# Athena-r1p0.net
KiCad netlist of a schematic drawn in EAGLE
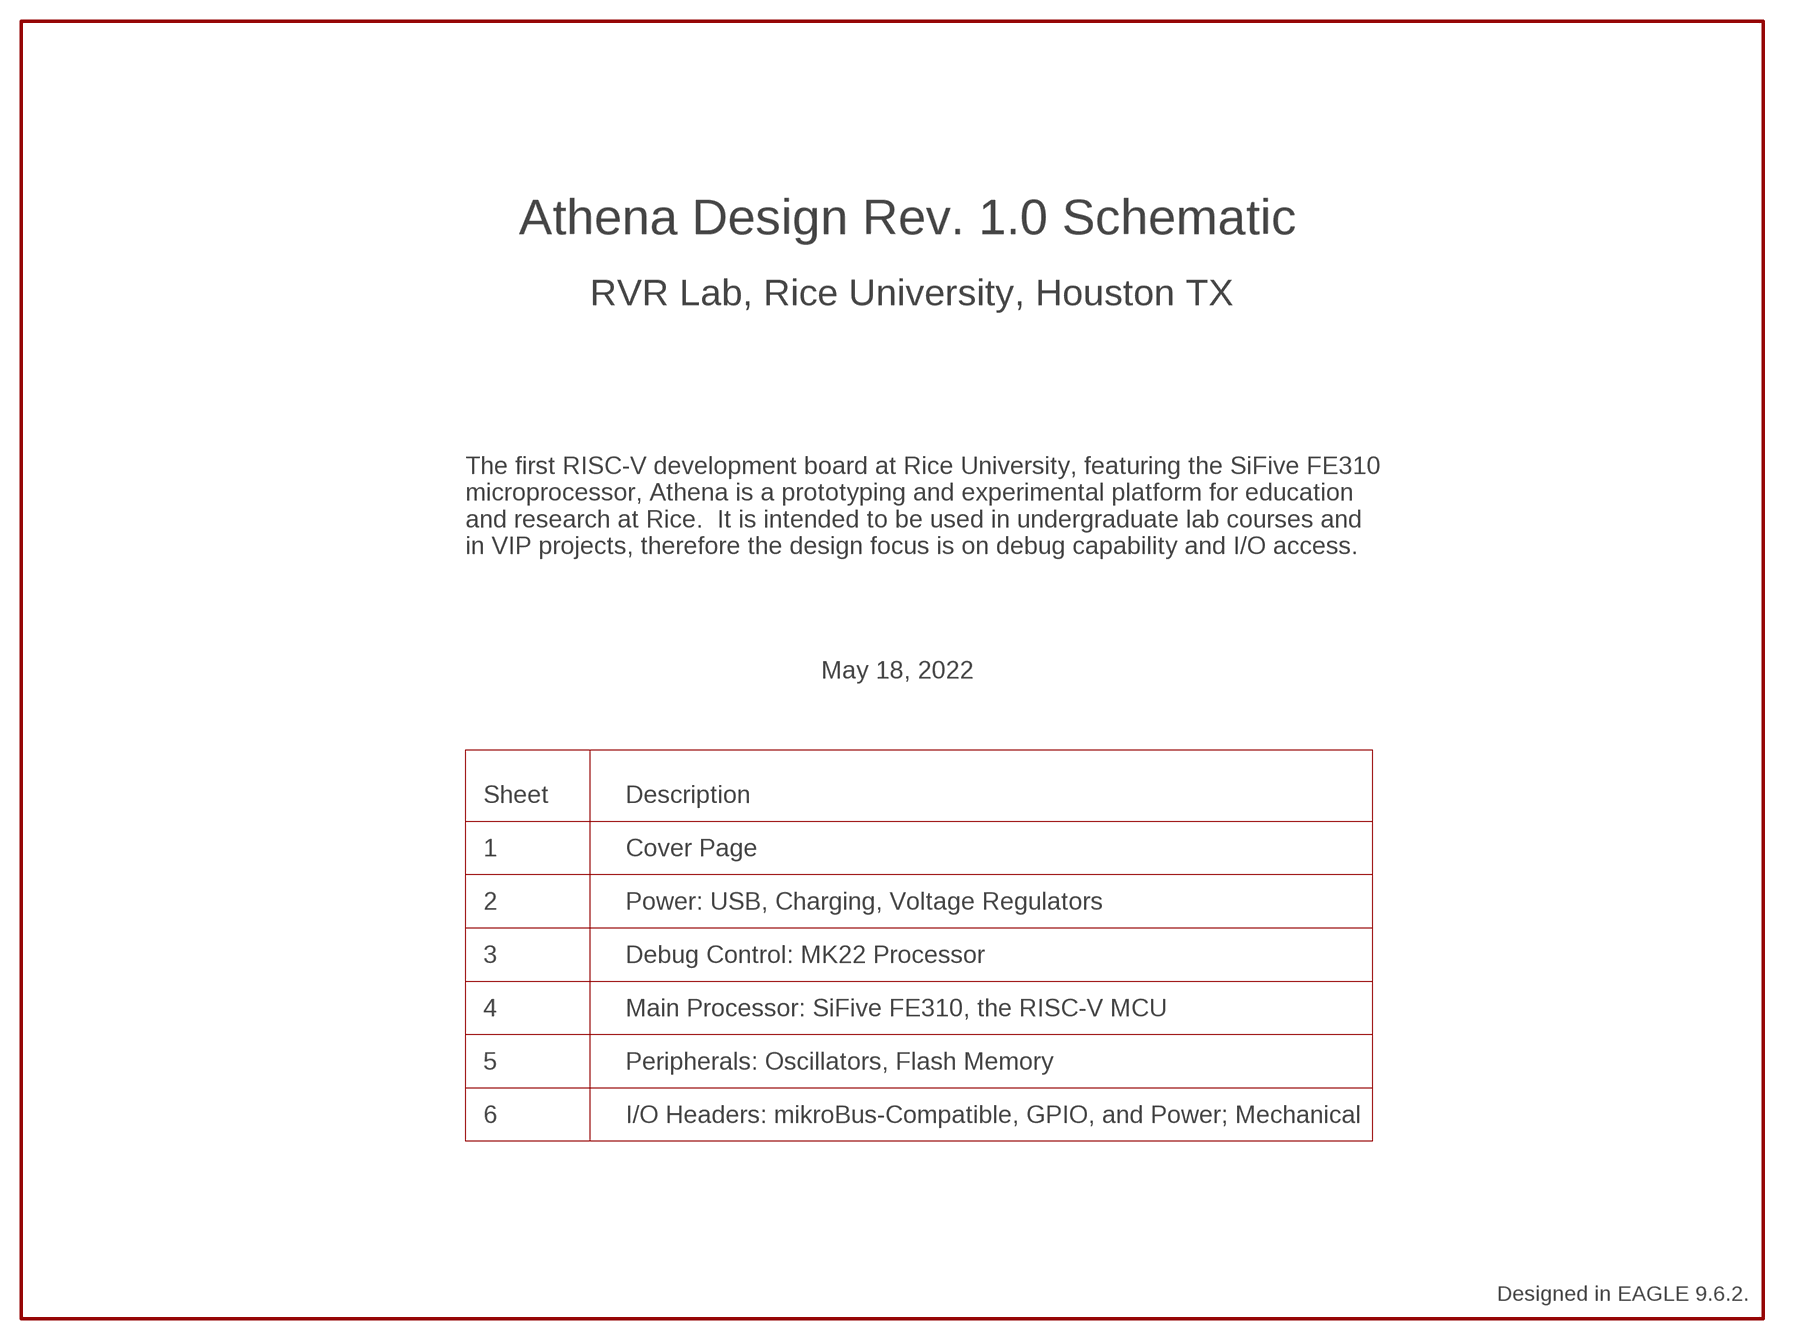
[diagram p0: schematic, sheet 1]
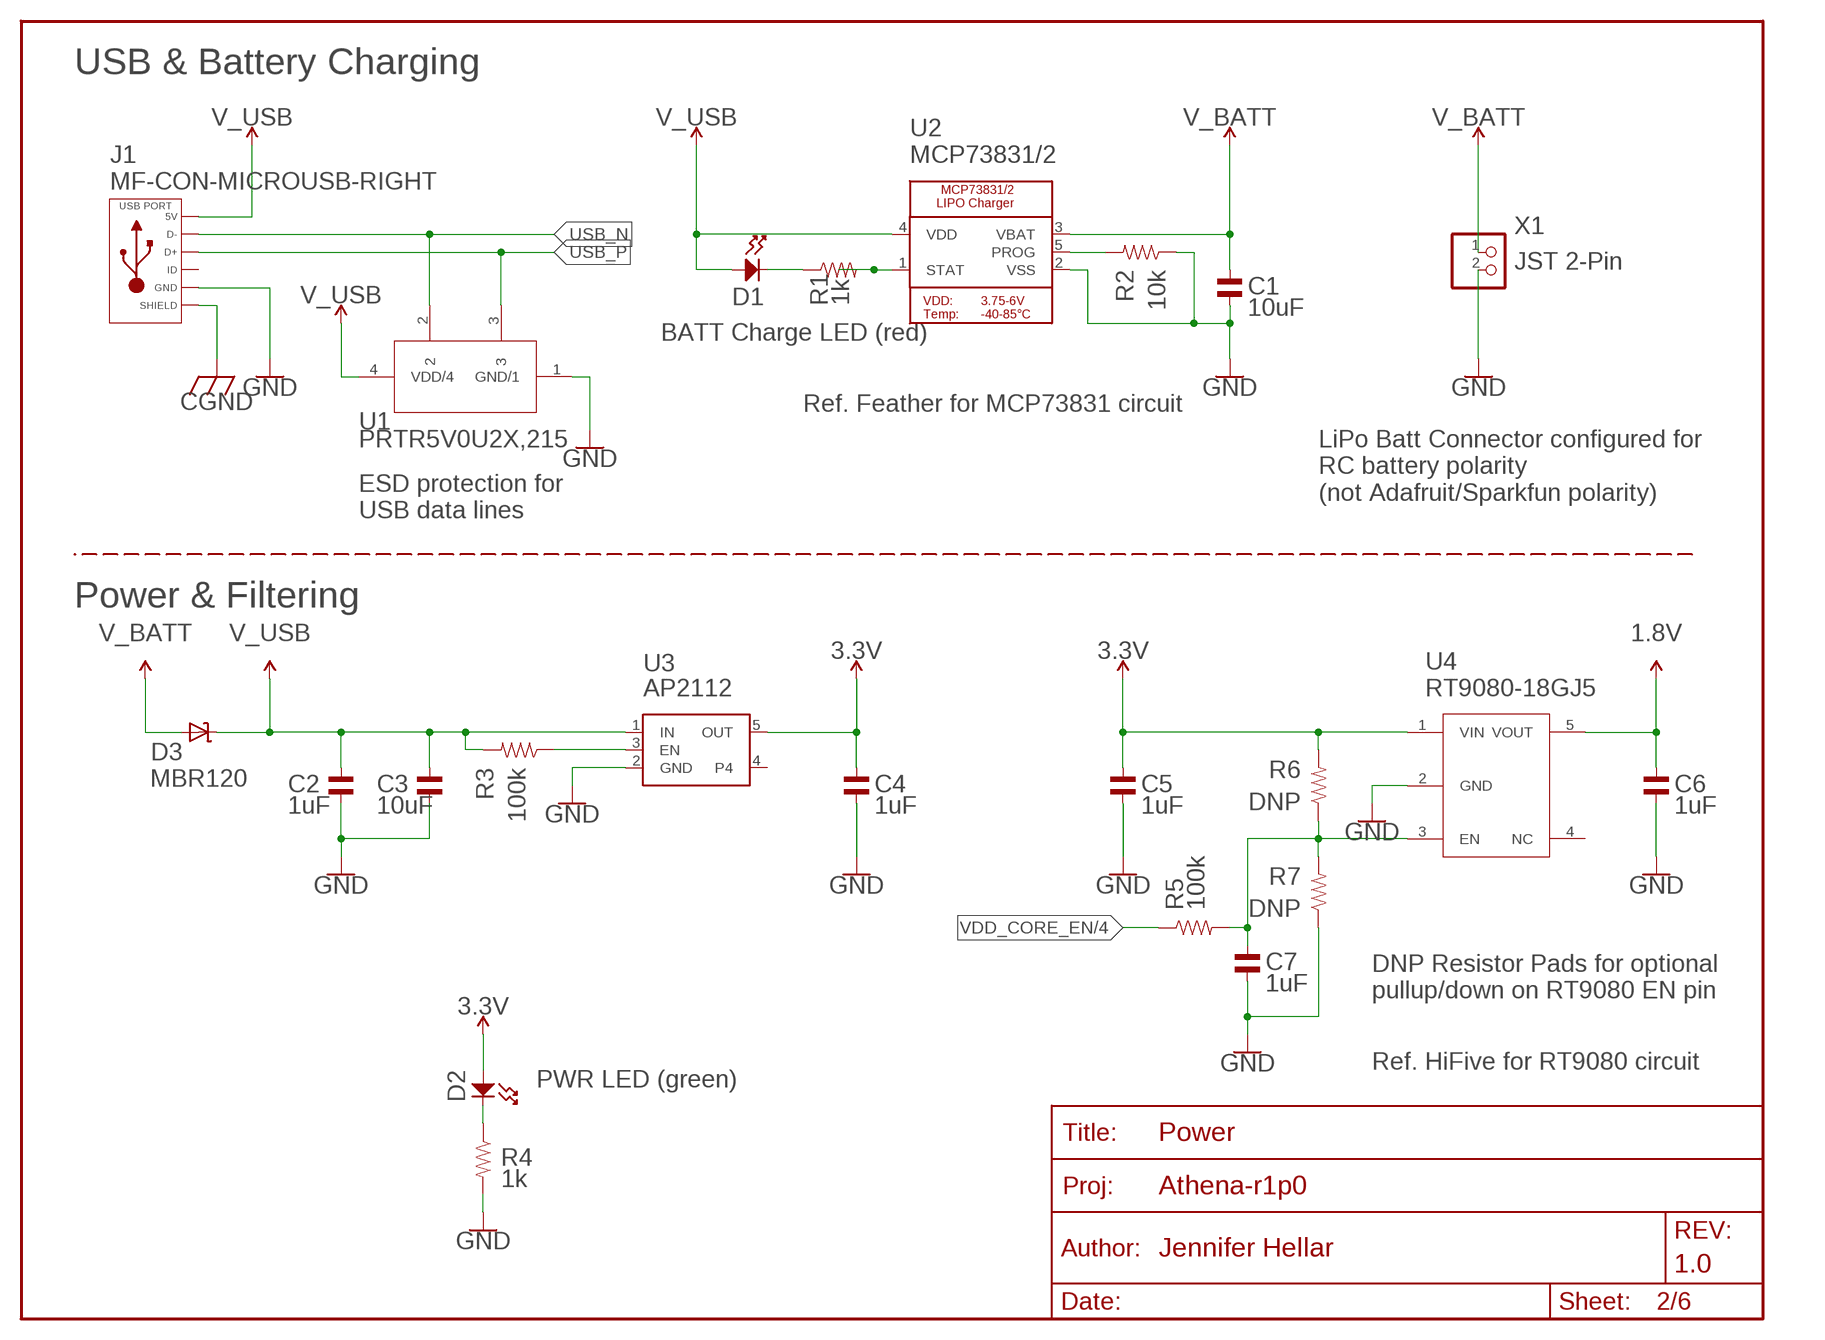
[diagram p1: schematic, sheet 2]
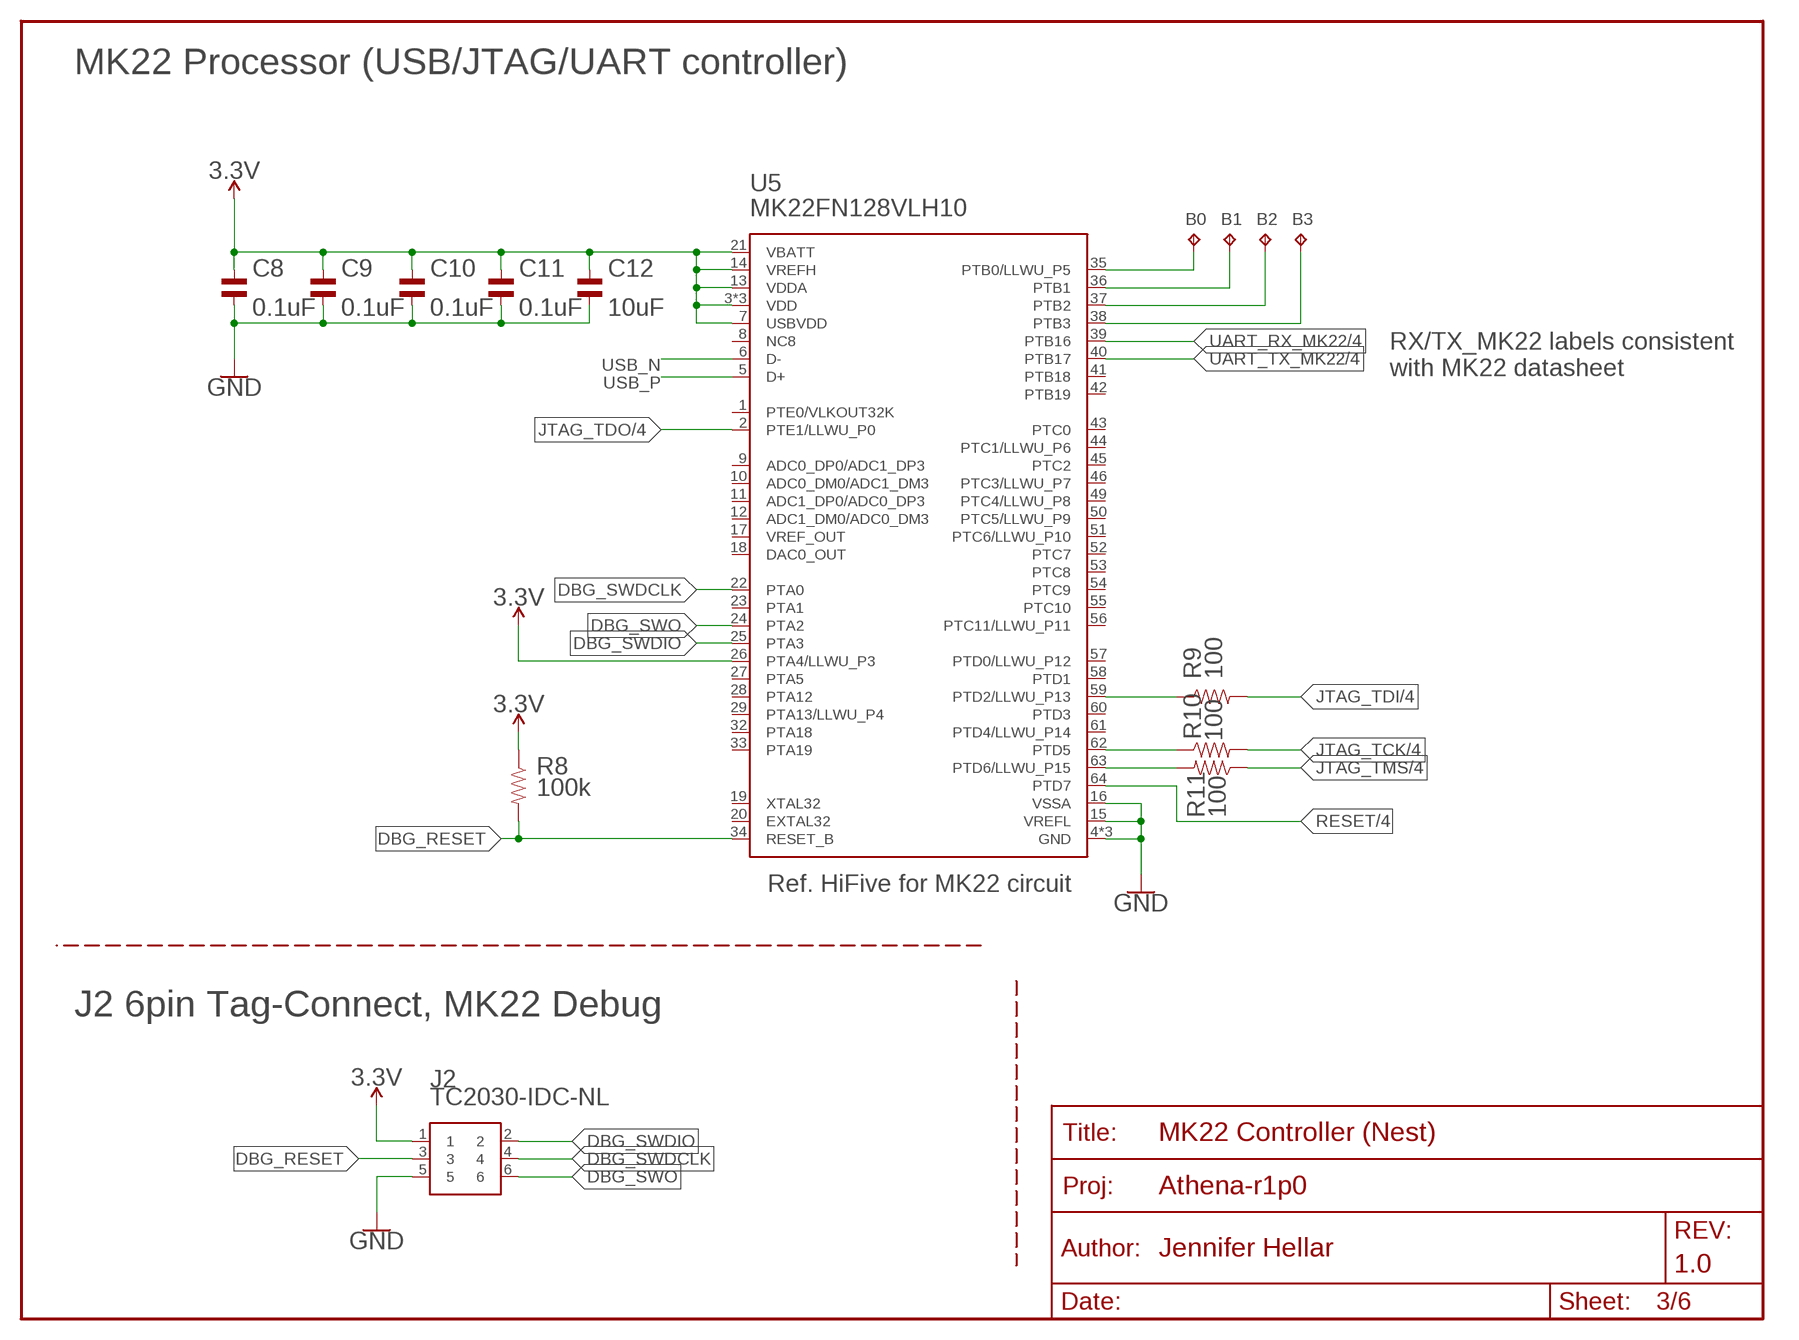
[diagram p2: schematic, sheet 3]
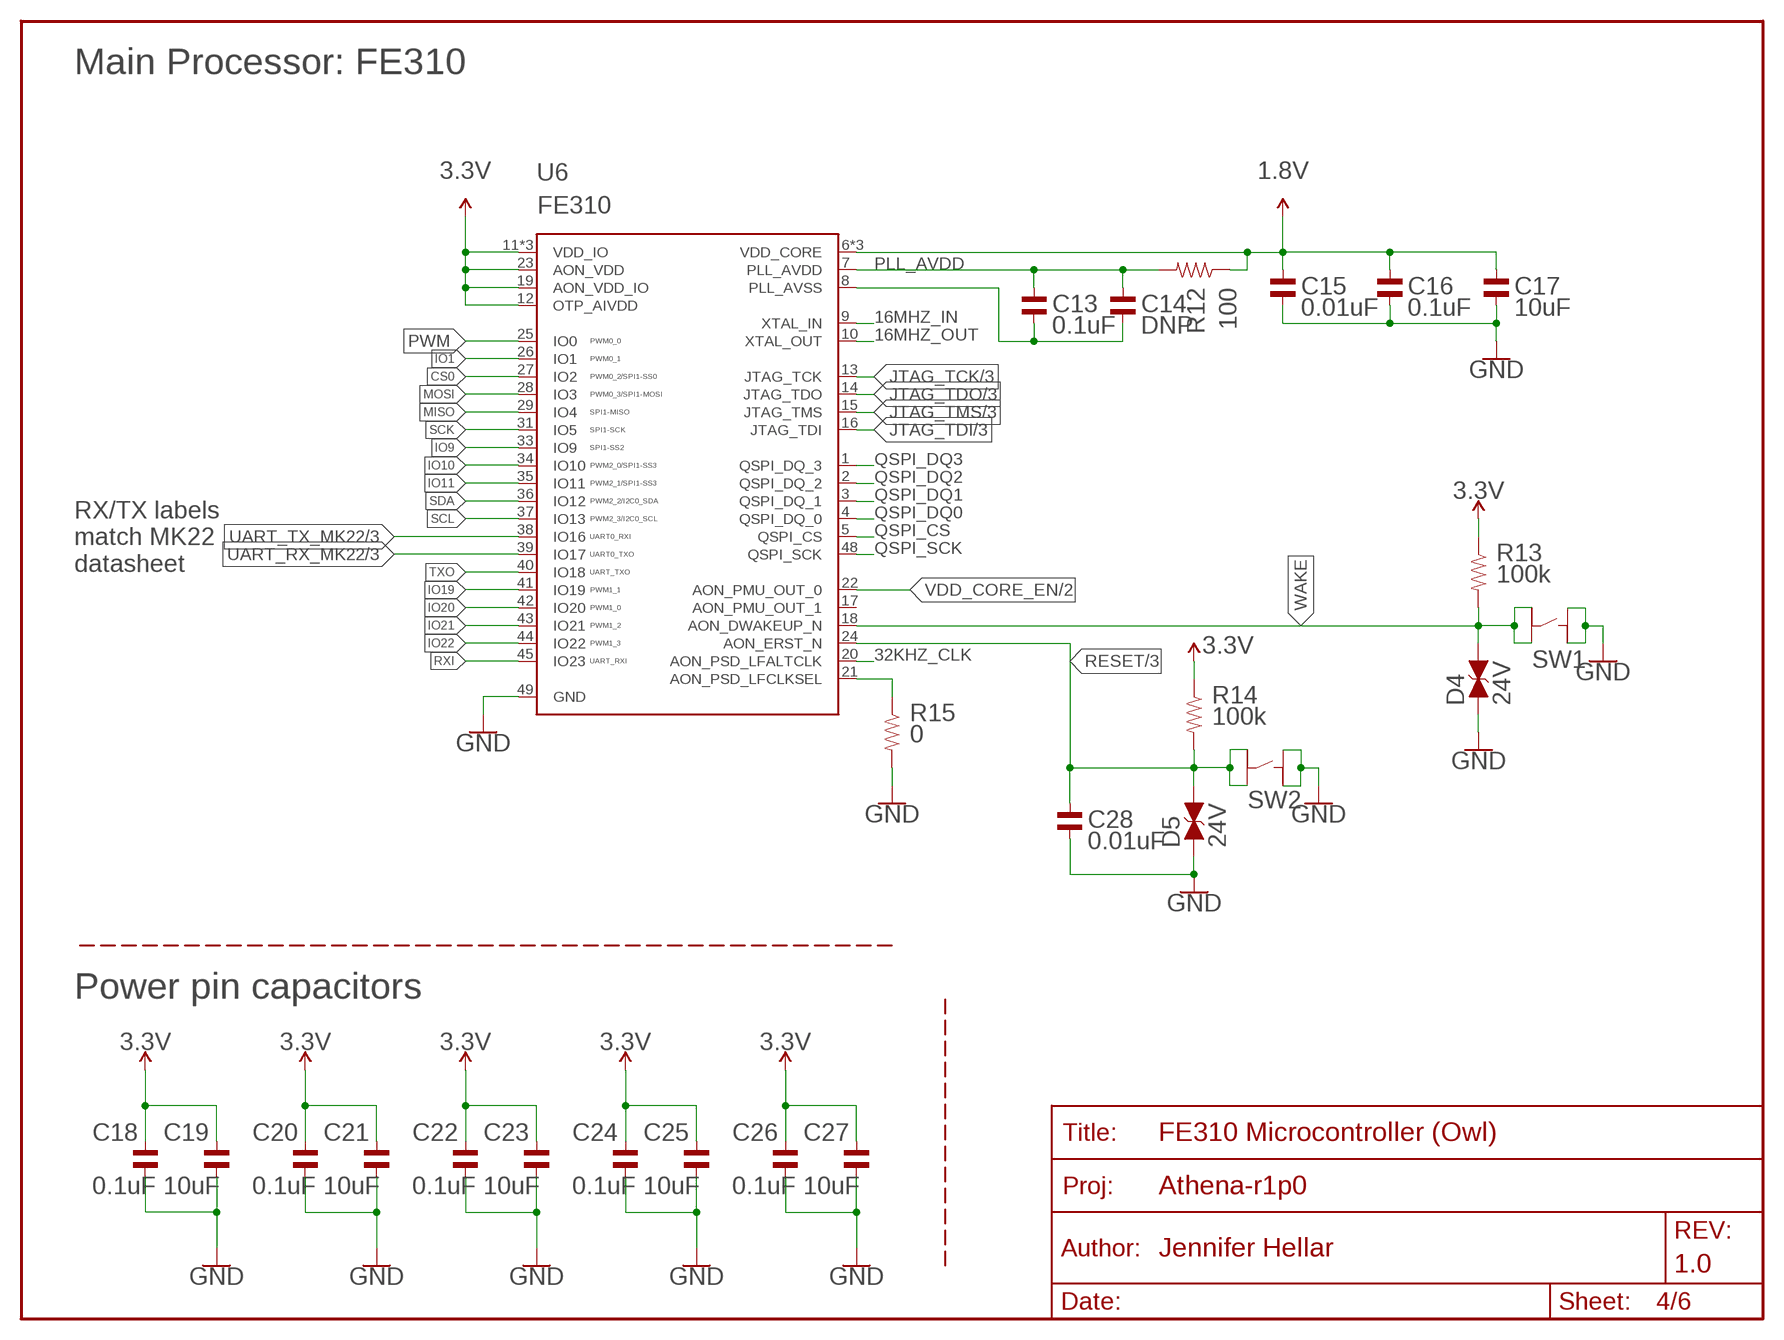
[diagram p3: schematic, sheet 4]
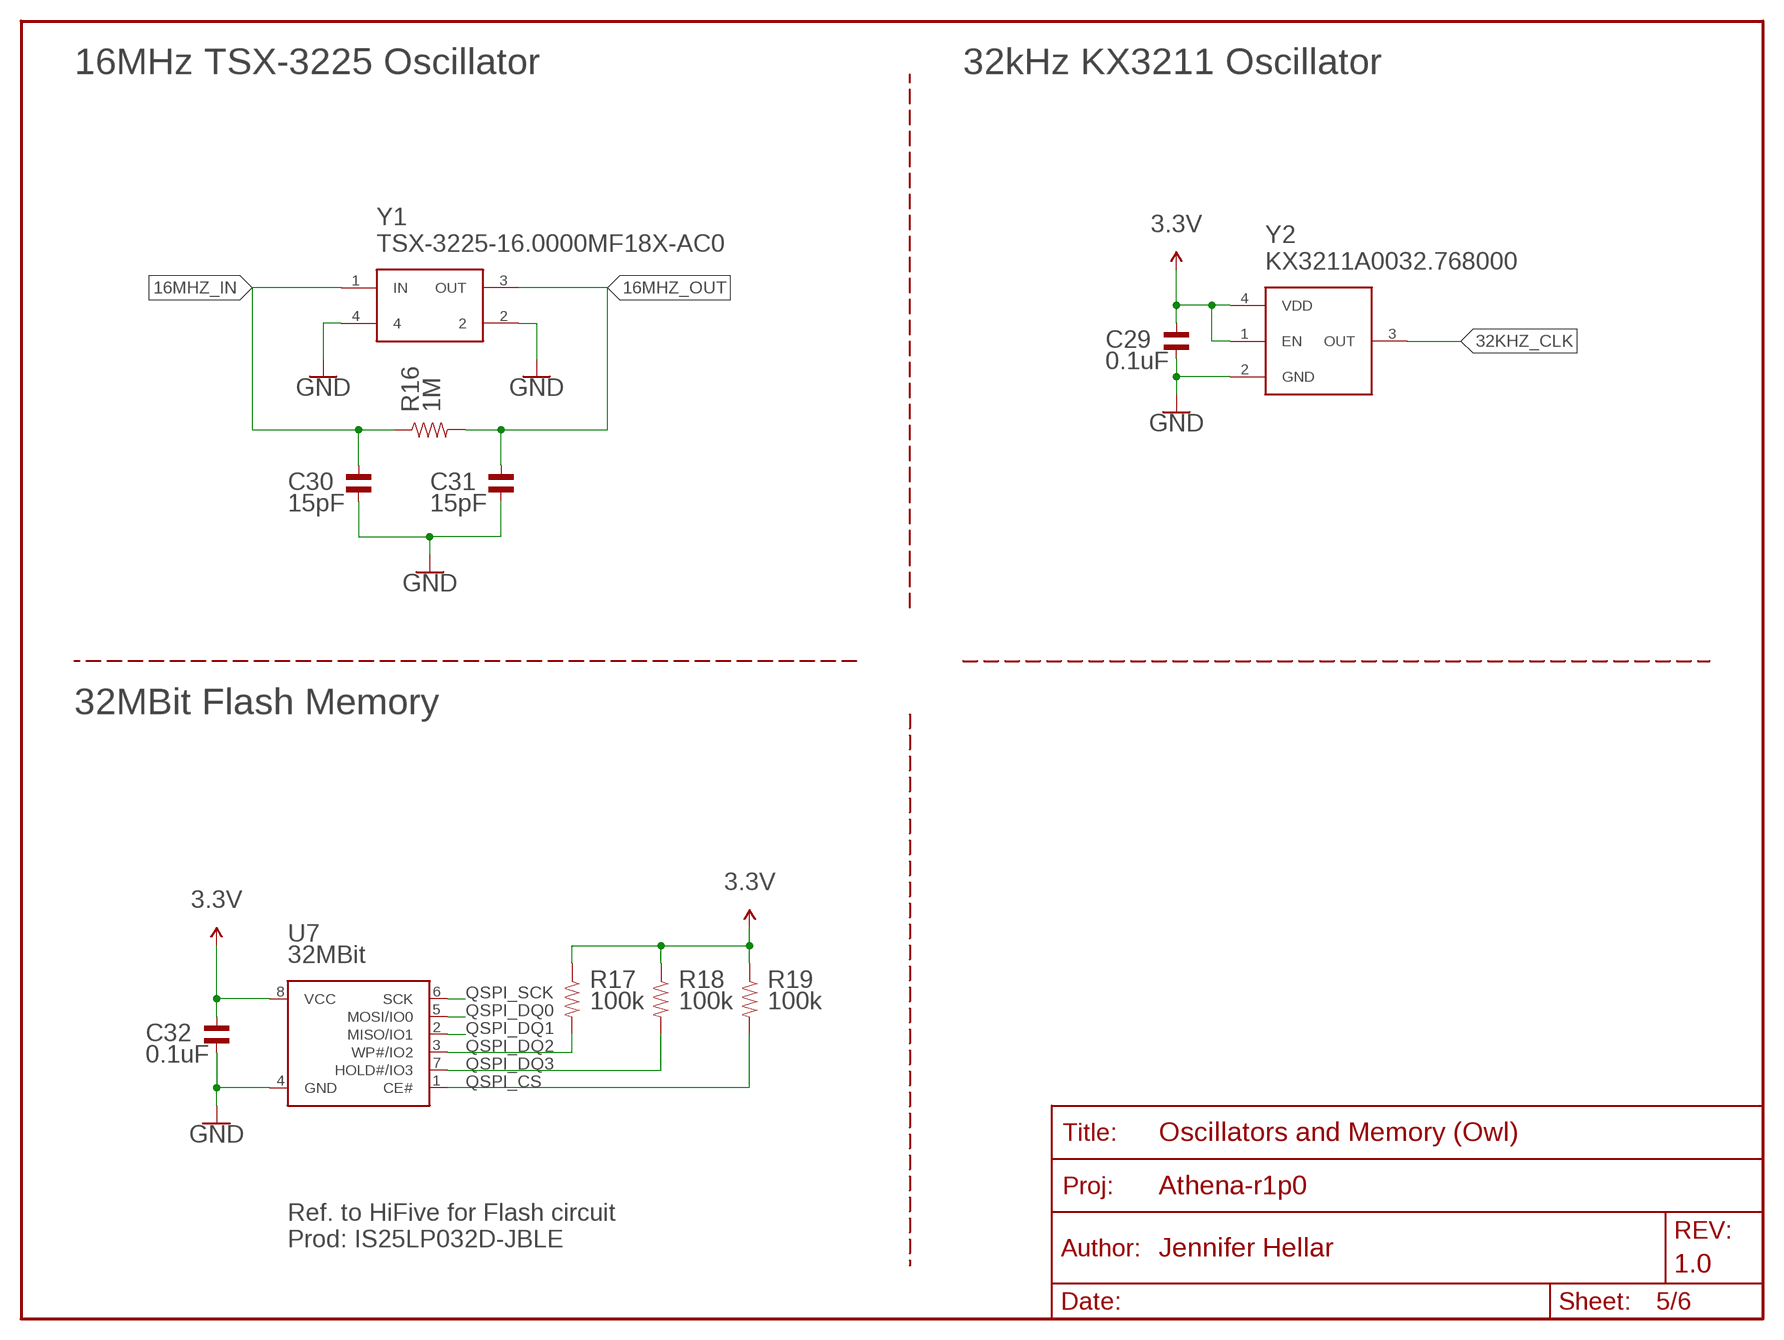
[diagram p4: schematic, sheet 5]
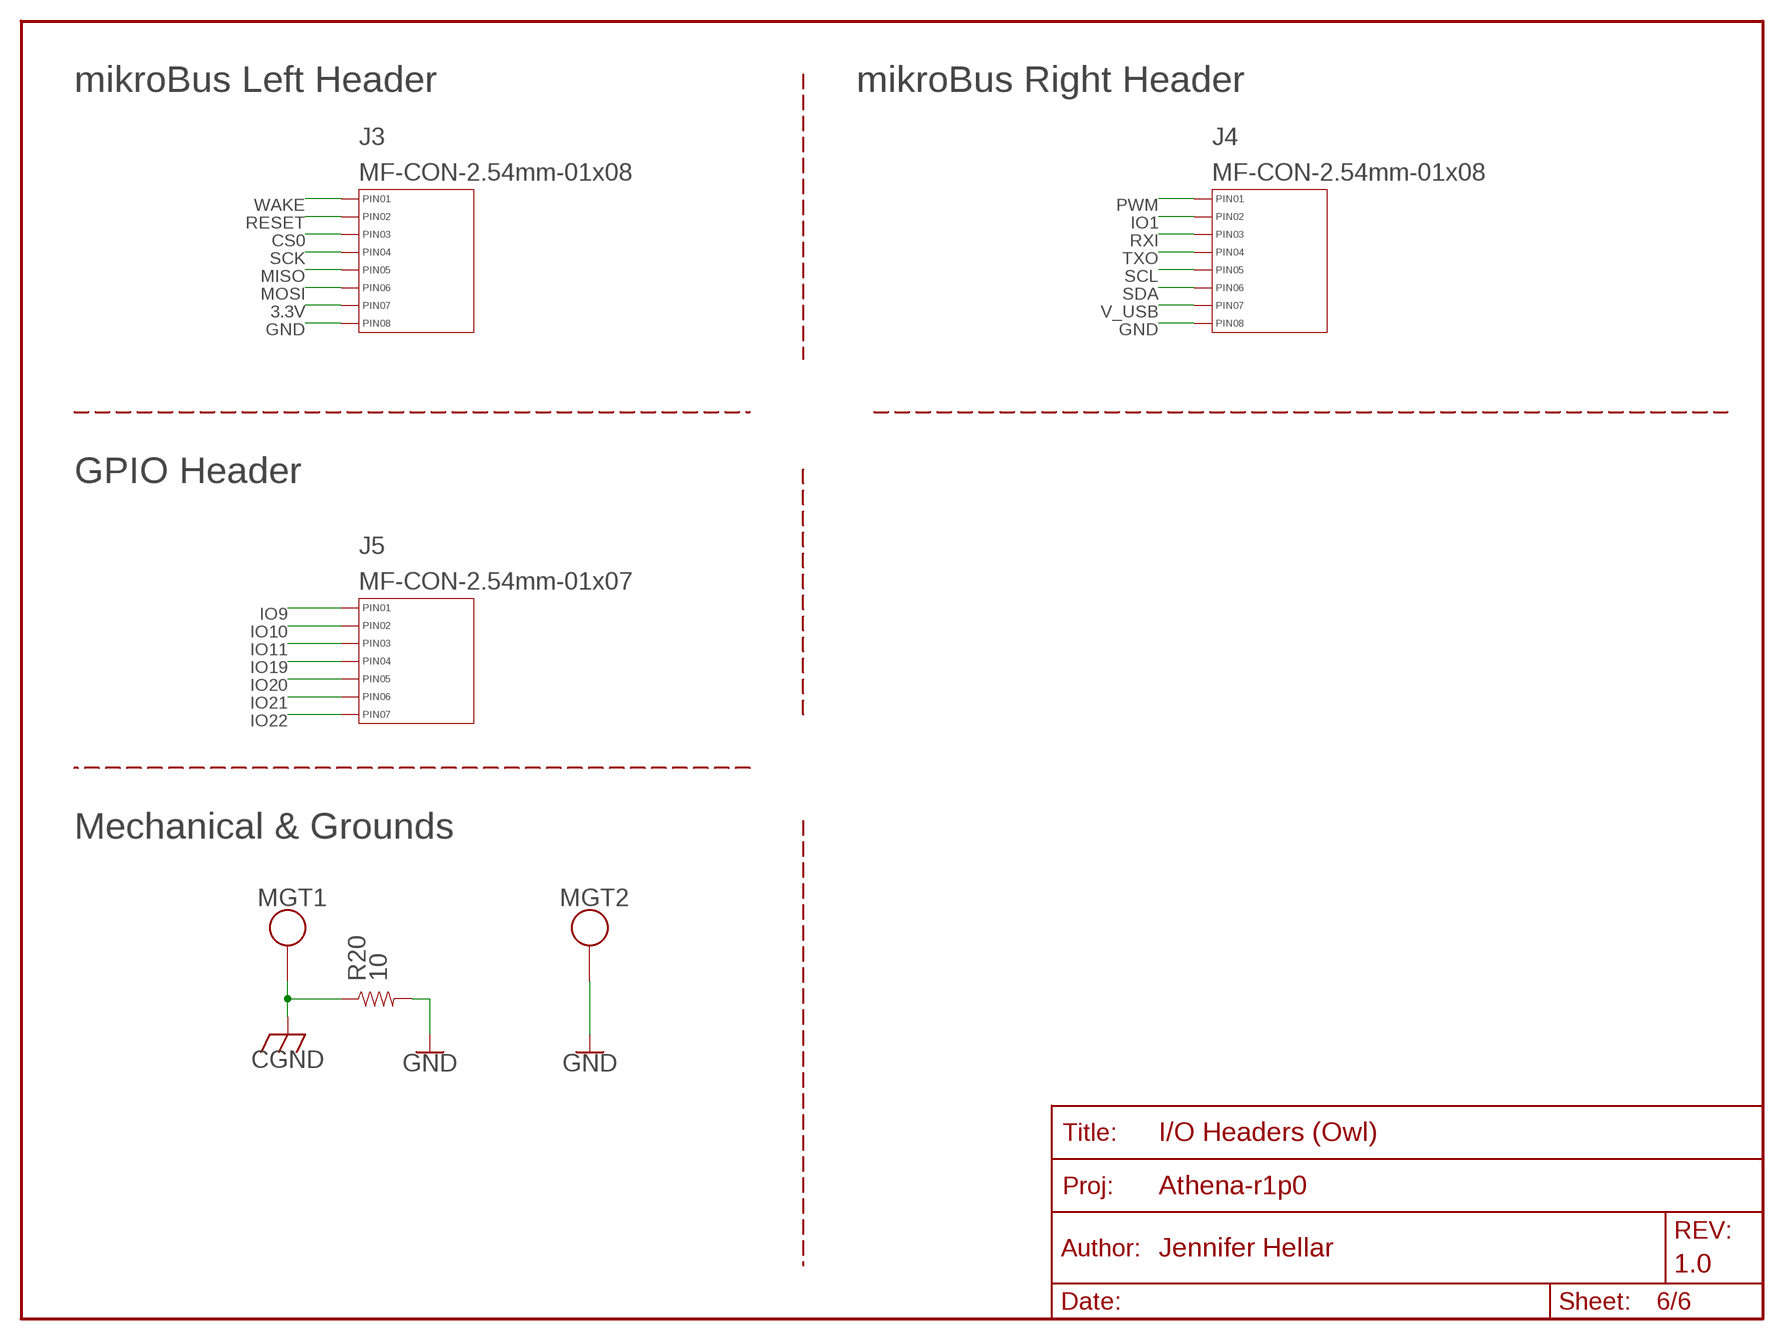
[diagram p5: schematic, sheet 6]

(export (version "E")
  (design (tool "Eeschema 10.0.6"))
  (components
    (comp (ref "C13")
      (value "0.1uF")
      (footprint "eagle-import:C0402")
      (libsource (lib "eagle-import") (part "CAPACITOR_NP_0402"))
    )
    (comp (ref "C14")
      (value "DNP")
      (footprint "eagle-import:C0402")
      (libsource (lib "eagle-import") (part "CAPACITOR_NP_0402"))
    )
    (comp (ref "C15")
      (value "0.01uF")
      (footprint "eagle-import:C0402")
      (libsource (lib "eagle-import") (part "CAPACITOR_NP_0402"))
    )
    (comp (ref "C16")
      (value "0.1uF")
      (footprint "eagle-import:C0402")
      (libsource (lib "eagle-import") (part "CAPACITOR_NP_0402"))
    )
    (comp (ref "C17")
      (value "10uF")
      (footprint "eagle-import:C0402")
      (fields (field (name "MPN") "CL05A106MP8NUB8"))
      (libsource (lib "eagle-import") (part "CAPACITOR_NP_0402"))
    )
    (comp (ref "C18")
      (value "0.1uF")
      (footprint "eagle-import:C0402")
      (libsource (lib "eagle-import") (part "CAPACITOR_NP_0402"))
    )
    (comp (ref "C19")
      (value "10uF")
      (footprint "eagle-import:C0402")
      (fields (field (name "MPN") "CL05A106MP8NUB8"))
      (libsource (lib "eagle-import") (part "CAPACITOR_NP_0402"))
    )
    (comp (ref "C20")
      (value "0.1uF")
      (footprint "eagle-import:C0402")
      (libsource (lib "eagle-import") (part "CAPACITOR_NP_0402"))
    )
    (comp (ref "C21")
      (value "10uF")
      (footprint "eagle-import:C0402")
      (fields (field (name "MPN") "CL05A106MP8NUB8"))
      (libsource (lib "eagle-import") (part "CAPACITOR_NP_0402"))
    )
    (comp (ref "C22")
      (value "0.1uF")
      (footprint "eagle-import:C0402")
      (libsource (lib "eagle-import") (part "CAPACITOR_NP_0402"))
    )
    (comp (ref "C23")
      (value "10uF")
      (footprint "eagle-import:C0402")
      (fields (field (name "MPN") "CL05A106MP8NUB8"))
      (libsource (lib "eagle-import") (part "CAPACITOR_NP_0402"))
    )
    (comp (ref "C24")
      (value "0.1uF")
      (footprint "eagle-import:C0402")
      (libsource (lib "eagle-import") (part "CAPACITOR_NP_0402"))
    )
    (comp (ref "C25")
      (value "10uF")
      (footprint "eagle-import:C0402")
      (fields (field (name "MPN") "CL05A106MP8NUB8"))
      (libsource (lib "eagle-import") (part "CAPACITOR_NP_0402"))
    )
    (comp (ref "C26")
      (value "0.1uF")
      (footprint "eagle-import:C0402")
      (libsource (lib "eagle-import") (part "CAPACITOR_NP_0402"))
    )
    (comp (ref "C27")
      (value "10uF")
      (footprint "eagle-import:C0402")
      (fields (field (name "MPN") "CL05A106MP8NUB8"))
      (libsource (lib "eagle-import") (part "CAPACITOR_NP_0402"))
    )
    (comp (ref "C28")
      (value "0.01uF")
      (footprint "eagle-import:C0402")
      (libsource (lib "eagle-import") (part "CAPACITOR_NP_0402"))
    )
    (comp (ref "D4")
      (value "24V")
      (footprint "eagle-import:TVS0603")
      (libsource (lib "eagle-import") (part "PESD0603-240TVS0603"))
    )
    (comp (ref "D5")
      (value "24V")
      (footprint "eagle-import:TVS0603")
      (libsource (lib "eagle-import") (part "PESD0603-240TVS0603"))
    )
    (comp (ref "R12")
      (value "100")
      (footprint "eagle-import:R0402")
      (libsource (lib "eagle-import") (part "RESISTOR_0402"))
    )
    (comp (ref "R13")
      (value "100k")
      (footprint "eagle-import:R0402")
      (libsource (lib "eagle-import") (part "RESISTOR_0402"))
    )
    (comp (ref "R14")
      (value "100k")
      (footprint "eagle-import:R0402")
      (libsource (lib "eagle-import") (part "RESISTOR_0402"))
    )
    (comp (ref "R15")
      (value "0")
      (footprint "eagle-import:R0402")
      (libsource (lib "eagle-import") (part "RESISTOR_0402"))
    )
    (comp (ref "SW1")
      (value "MF-SW-TACT-6MM")
      (footprint "eagle-import:TACT4.2MM")
      (fields (field (name "HOUSEPART") "YES"))
      (libsource (lib "eagle-import") (part "TACT_4.2MM"))
    )
    (comp (ref "SW2")
      (value "MF-SW-TACT-6MM")
      (footprint "eagle-import:TACT4.2MM")
      (fields (field (name "HOUSEPART") "YES"))
      (libsource (lib "eagle-import") (part "TACT_4.2MM"))
    )
    (comp (ref "U6")
      (value "FE310")
      (footprint "eagle-import:MCU_QFN-48-.4MMPITCH")
      (libsource (lib "eagle-import") (part "IC_MCU_SIFIVE_FE310"))
    )
    (comp (ref "C29")
      (value "0.1uF")
      (footprint "eagle-import:C0402")
      (libsource (lib "eagle-import") (part "CAPACITOR_NP_0402"))
    )
    (comp (ref "C30")
      (value "15pF")
      (footprint "eagle-import:C0402")
      (fields (field (name "MPN") "CL05C150JB5NNNC"))
      (libsource (lib "eagle-import") (part "CAPACITOR_NP_0402"))
    )
    (comp (ref "C31")
      (value "15pF")
      (footprint "eagle-import:C0402")
      (fields (field (name "MPN") "CL05C150JB5NNNC"))
      (libsource (lib "eagle-import") (part "CAPACITOR_NP_0402"))
    )
    (comp (ref "C32")
      (value "0.1uF")
      (footprint "eagle-import:C0402")
      (libsource (lib "eagle-import") (part "CAPACITOR_NP_0402"))
    )
    (comp (ref "R16")
      (value "1M")
      (footprint "eagle-import:R0402")
      (libsource (lib "eagle-import") (part "RESISTOR_0402"))
    )
    (comp (ref "R17")
      (value "100k")
      (footprint "eagle-import:R0402")
      (libsource (lib "eagle-import") (part "RESISTOR_0402"))
    )
    (comp (ref "R18")
      (value "100k")
      (footprint "eagle-import:R0402")
      (libsource (lib "eagle-import") (part "RESISTOR_0402"))
    )
    (comp (ref "R19")
      (value "100k")
      (footprint "eagle-import:R0402")
      (libsource (lib "eagle-import") (part "RESISTOR_0402"))
    )
    (comp (ref "U7")
      (value "32MBit")
      (footprint "eagle-import:IC-MEMORY_SO08")
      (libsource (lib "eagle-import") (part "IC_MEMORY_QSPI32MBIT"))
    )
    (comp (ref "Y1")
      (value "TSX-3225-16.0000MF18X-AC0")
      (footprint "eagle-import:SMD-4")
      (libsource (lib "eagle-import") (part "TSX-3225-16.0000MF18X-AC0"))
    )
    (comp (ref "Y2")
      (value "KX3211A0032.768000")
      (footprint "eagle-import:SMD-4")
      (libsource (lib "eagle-import") (part "KX3211A0032.768000"))
    )
    (comp (ref "C1")
      (value "10uF")
      (footprint "eagle-import:C0402")
      (fields (field (name "MPN") "CL05A106MP8NUB8"))
      (libsource (lib "eagle-import") (part "CAPACITOR_NP_0402"))
    )
    (comp (ref "C2")
      (value "1uF")
      (footprint "eagle-import:C0402")
      (libsource (lib "eagle-import") (part "CAPACITOR_NP_0402"))
    )
    (comp (ref "C3")
      (value "10uF")
      (footprint "eagle-import:C0402")
      (fields (field (name "MPN") "CL05A106MP8NUB8"))
      (libsource (lib "eagle-import") (part "CAPACITOR_NP_0402"))
    )
    (comp (ref "C4")
      (value "1uF")
      (footprint "eagle-import:C0402")
      (libsource (lib "eagle-import") (part "CAPACITOR_NP_0402"))
    )
    (comp (ref "C5")
      (value "1uF")
      (footprint "eagle-import:C0402")
      (libsource (lib "eagle-import") (part "CAPACITOR_NP_0402"))
    )
    (comp (ref "C6")
      (value "1uF")
      (footprint "eagle-import:C0402")
      (libsource (lib "eagle-import") (part "CAPACITOR_NP_0402"))
    )
    (comp (ref "C7")
      (value "1uF")
      (footprint "eagle-import:C0402")
      (libsource (lib "eagle-import") (part "CAPACITOR_NP_0402"))
    )
    (comp (ref "D1")
      (value "MF-LED-0805-RED")
      (footprint "eagle-import:LED0603")
      (fields (field (name "HOUSEPART") "YES"))
      (libsource (lib "eagle-import") (part "LED_SINGLE-0603-RED"))
    )
    (comp (ref "D2")
      (value "MF-LED-0603-GREEN")
      (footprint "eagle-import:LED0603")
      (fields (field (name "HOUSEPART") "YES"))
      (libsource (lib "eagle-import") (part "LED_SINGLE-0603-GREEN"))
    )
    (comp (ref "D3")
      (value "MBR120")
      (footprint "eagle-import:SOD-123")
      (libsource (lib "eagle-import") (part "DIODE-SCHOTTKYSOD-123"))
    )
    (comp (ref "J1")
      (value "MF-CON-MICROUSB-RIGHT")
      (footprint "eagle-import:MICROUSB-RIGHT")
      (fields (field (name "HOUSEPART") "YES") (field (name "HUOSEPART") "NO"))
      (libsource (lib "eagle-import") (part "USB_MICRO_RIGHT"))
    )
    (comp (ref "R1")
      (value "1k")
      (footprint "eagle-import:R0402")
      (libsource (lib "eagle-import") (part "RESISTOR_0402"))
    )
    (comp (ref "R2")
      (value "10k")
      (footprint "eagle-import:R0402")
      (libsource (lib "eagle-import") (part "RESISTOR_0402"))
    )
    (comp (ref "R3")
      (value "100k")
      (footprint "eagle-import:R0402")
      (libsource (lib "eagle-import") (part "RESISTOR_0402"))
    )
    (comp (ref "R4")
      (value "1k")
      (footprint "eagle-import:R0402")
      (libsource (lib "eagle-import") (part "RESISTOR_0402"))
    )
    (comp (ref "R5")
      (value "100k")
      (footprint "eagle-import:R0402")
      (libsource (lib "eagle-import") (part "RESISTOR_0402"))
    )
    (comp (ref "R6")
      (value "DNP")
      (footprint "eagle-import:R0402")
      (libsource (lib "eagle-import") (part "RESISTOR_0402"))
    )
    (comp (ref "R7")
      (value "DNP")
      (footprint "eagle-import:R0402")
      (libsource (lib "eagle-import") (part "RESISTOR_0402"))
    )
    (comp (ref "U1")
      (value "PRTR5V0U2X,215")
      (footprint "eagle-import:SOT143B_PRTR5V0U2X,215_NEX")
      (fields (field (name "COPYRIGHT") "Copyright (C) 2021 Ultra Librarian. All rights reserved."))
      (libsource (lib "eagle-import") (part "PRTR5V0U2X,215"))
    )
    (comp (ref "U2")
      (value "MCP73831/2")
      (footprint "eagle-import:SOT23-5")
      (libsource (lib "eagle-import") (part "MCP73831/2"))
    )
    (comp (ref "U3")
      (value "AP2112")
      (footprint "eagle-import:SOT23-5")
      (libsource (lib "eagle-import") (part "AP2112"))
    )
    (comp (ref "U4")
      (value "RT9080-18GJ5")
      (footprint "eagle-import:TSOT23-5_ONS")
      (libsource (lib "eagle-import") (part "RT9080-18GJ5"))
    )
    (comp (ref "X1")
      (value "JST 2-Pin")
      (footprint "eagle-import:JSTPH2")
      (libsource (lib "eagle-import") (part "CONNECTORS_BATT_JST_PH_2PIN"))
    )
    (comp (ref "J3")
      (value "MF-CON-2.54mm-01x08")
      (footprint "eagle-import:PTH_2.54MM_01X08")
      (fields (field (name "HOUSEPART") "YES"))
      (libsource (lib "eagle-import") (part "CON_01X08_PTH_2.54MM"))
    )
    (comp (ref "J4")
      (value "MF-CON-2.54mm-01x08")
      (footprint "eagle-import:PTH_2.54MM_01X08")
      (fields (field (name "HOUSEPART") "YES"))
      (libsource (lib "eagle-import") (part "CON_01X08_PTH_2.54MM"))
    )
    (comp (ref "J5")
      (value "MF-CON-2.54mm-01x07")
      (footprint "eagle-import:PTH_2.54MM_01X07")
      (fields (field (name "HOUSEPART") "YES"))
      (libsource (lib "eagle-import") (part "CON_01X07_PTH_2.54MM"))
    )
    (comp (ref "MGT1")
      (value "MOUNTING_HOLE")
      (footprint "eagle-import:MOUNTING_HOLE")
      (libsource (lib "eagle-import") (part "MOUNTING_HOLE"))
    )
    (comp (ref "MGT2")
      (value "MOUNTING_HOLE")
      (footprint "eagle-import:MOUNTING_HOLE")
      (libsource (lib "eagle-import") (part "MOUNTING_HOLE"))
    )
    (comp (ref "R20")
      (value "10")
      (footprint "eagle-import:R0402")
      (libsource (lib "eagle-import") (part "RESISTOR_0402"))
    )
    (comp (ref "B0")
      (value "TPB0,65")
      (footprint "eagle-import:TP_B0,65")
      (libsource (lib "eagle-import") (part "TPB0,65"))
    )
    (comp (ref "B1")
      (value "TPB0,65")
      (footprint "eagle-import:TP_B0,65")
      (libsource (lib "eagle-import") (part "TPB0,65"))
    )
    (comp (ref "B2")
      (value "TPB0,65")
      (footprint "eagle-import:TP_B0,65")
      (libsource (lib "eagle-import") (part "TPB0,65"))
    )
    (comp (ref "B3")
      (value "TPB0,65")
      (footprint "eagle-import:TP_B0,65")
      (libsource (lib "eagle-import") (part "TPB0,65"))
    )
    (comp (ref "C8")
      (value "0.1uF")
      (footprint "eagle-import:C0402")
      (libsource (lib "eagle-import") (part "CAPACITOR_NP_0402"))
    )
    (comp (ref "C9")
      (value "0.1uF")
      (footprint "eagle-import:C0402")
      (libsource (lib "eagle-import") (part "CAPACITOR_NP_0402"))
    )
    (comp (ref "C10")
      (value "0.1uF")
      (footprint "eagle-import:C0402")
      (libsource (lib "eagle-import") (part "CAPACITOR_NP_0402"))
    )
    (comp (ref "C11")
      (value "0.1uF")
      (footprint "eagle-import:C0402")
      (libsource (lib "eagle-import") (part "CAPACITOR_NP_0402"))
    )
    (comp (ref "C12")
      (value "10uF")
      (footprint "eagle-import:C0402")
      (fields (field (name "MPN") "CL05A106MP8NUB8"))
      (libsource (lib "eagle-import") (part "CAPACITOR_NP_0402"))
    )
    (comp (ref "J2")
      (value "TC2030-IDC-NL")
      (footprint "eagle-import:TAG_TC2030-IDC-NL")
      (fields (field (name "MF") "Tag-Connect"))
      (libsource (lib "eagle-import") (part "TC2030-IDC-NL"))
    )
    (comp (ref "R8")
      (value "100k")
      (footprint "eagle-import:R0402")
      (libsource (lib "eagle-import") (part "RESISTOR_0402"))
    )
    (comp (ref "R9")
      (value "100")
      (footprint "eagle-import:R0402")
      (libsource (lib "eagle-import") (part "RESISTOR_0402"))
    )
    (comp (ref "R10")
      (value "100")
      (footprint "eagle-import:R0402")
      (libsource (lib "eagle-import") (part "RESISTOR_0402"))
    )
    (comp (ref "R11")
      (value "100")
      (footprint "eagle-import:R0402")
      (libsource (lib "eagle-import") (part "RESISTOR_0402"))
    )
    (comp (ref "U5")
      (value "MK22FN128VLH10")
      (footprint "eagle-import:IC_USB_JTAG_LQFP-64")
      (libsource (lib "eagle-import") (part "MK22FN128VLH10"))
    )
  )
  (nets
    (net (code "1") (name "1.8V") (class "Default")
      (node (ref "C15") (pin "P$1") (pinfunction "P$1_P$1") (pintype "passive"))
      (node (ref "C16") (pin "P$1") (pinfunction "P$1_P$1") (pintype "passive"))
      (node (ref "C17") (pin "P$1") (pinfunction "P$1_P$1") (pintype "passive"))
      (node (ref "C6") (pin "P$1") (pinfunction "P$1_P$1") (pintype "passive"))
      (node (ref "R12") (pin "P$1") (pinfunction "P$1_P$1") (pintype "passive"))
      (node (ref "U4") (pin "5") (pinfunction "VOUT_5") (pintype "passive"))
      (node (ref "U6") (pin "30") (pinfunction "VDD_CORE_30") (pintype "bidirectional"))
      (node (ref "U6") (pin "46") (pinfunction "VDD_CORE_46") (pintype "bidirectional"))
      (node (ref "U6") (pin "6") (pinfunction "VDD_CORE_6") (pintype "bidirectional"))
    )
    (net (code "2") (name "3.3V") (class "Default")
      (node (ref "C10") (pin "P$1") (pinfunction "P$1_P$1") (pintype "passive"))
      (node (ref "C11") (pin "P$1") (pinfunction "P$1_P$1") (pintype "passive"))
      (node (ref "C12") (pin "P$1") (pinfunction "P$1_P$1") (pintype "passive"))
      (node (ref "C18") (pin "P$1") (pinfunction "P$1_P$1") (pintype "passive"))
      (node (ref "C19") (pin "P$1") (pinfunction "P$1_P$1") (pintype "passive"))
      (node (ref "C20") (pin "P$1") (pinfunction "P$1_P$1") (pintype "passive"))
      (node (ref "C21") (pin "P$1") (pinfunction "P$1_P$1") (pintype "passive"))
      (node (ref "C22") (pin "P$1") (pinfunction "P$1_P$1") (pintype "passive"))
      (node (ref "C23") (pin "P$1") (pinfunction "P$1_P$1") (pintype "passive"))
      (node (ref "C24") (pin "P$1") (pinfunction "P$1_P$1") (pintype "passive"))
      (node (ref "C25") (pin "P$1") (pinfunction "P$1_P$1") (pintype "passive"))
      (node (ref "C26") (pin "P$1") (pinfunction "P$1_P$1") (pintype "passive"))
      (node (ref "C27") (pin "P$1") (pinfunction "P$1_P$1") (pintype "passive"))
      (node (ref "C29") (pin "P$1") (pinfunction "P$1_P$1") (pintype "passive"))
      (node (ref "C32") (pin "P$1") (pinfunction "P$1_P$1") (pintype "passive"))
      (node (ref "C4") (pin "P$1") (pinfunction "P$1_P$1") (pintype "passive"))
      (node (ref "C5") (pin "P$1") (pinfunction "P$1_P$1") (pintype "passive"))
      (node (ref "C8") (pin "P$1") (pinfunction "P$1_P$1") (pintype "passive"))
      (node (ref "C9") (pin "P$1") (pinfunction "P$1_P$1") (pintype "passive"))
      (node (ref "D2") (pin "ANODE") (pinfunction "ANODE_ANODE") (pintype "power_in"))
      (node (ref "J2") (pin "1") (pinfunction "1_1") (pintype "passive"))
      (node (ref "J3") (pin "P$7") (pinfunction "PIN7_P$7") (pintype "bidirectional"))
      (node (ref "R13") (pin "P$1") (pinfunction "P$1_P$1") (pintype "passive"))
      (node (ref "R14") (pin "P$1") (pinfunction "P$1_P$1") (pintype "passive"))
      (node (ref "R17") (pin "P$1") (pinfunction "P$1_P$1") (pintype "passive"))
      (node (ref "R18") (pin "P$1") (pinfunction "P$1_P$1") (pintype "passive"))
      (node (ref "R19") (pin "P$1") (pinfunction "P$1_P$1") (pintype "passive"))
      (node (ref "R6") (pin "P$2") (pinfunction "P$2_P$2") (pintype "passive"))
      (node (ref "R8") (pin "P$1") (pinfunction "P$1_P$1") (pintype "passive"))
      (node (ref "U3") (pin "5") (pinfunction "OUT_5") (pintype "power_in"))
      (node (ref "U4") (pin "1") (pinfunction "VIN_1") (pintype "passive"))
      (node (ref "U5") (pin "13") (pinfunction "VDDA_13") (pintype "bidirectional"))
      (node (ref "U5") (pin "14") (pinfunction "VREFH_14") (pintype "bidirectional"))
      (node (ref "U5") (pin "21") (pinfunction "VBATT_21") (pintype "bidirectional"))
      (node (ref "U5") (pin "26") (pinfunction "PTA4/LLWU_P3_26") (pintype "bidirectional"))
      (node (ref "U5") (pin "3") (pinfunction "VDD_3") (pintype "bidirectional"))
      (node (ref "U5") (pin "30") (pinfunction "VDD_30") (pintype "bidirectional"))
      (node (ref "U5") (pin "48") (pinfunction "VDD_48") (pintype "bidirectional"))
      (node (ref "U5") (pin "7") (pinfunction "USBVDD_7") (pintype "bidirectional"))
      (node (ref "U6") (pin "11") (pinfunction "VDD_IO_11") (pintype "bidirectional"))
      (node (ref "U6") (pin "12") (pinfunction "OTP_AIVDD_12") (pintype "bidirectional"))
      (node (ref "U6") (pin "19") (pinfunction "AON_VDD_IO_19") (pintype "bidirectional"))
      (node (ref "U6") (pin "23") (pinfunction "AON_VDD_23") (pintype "bidirectional"))
      (node (ref "U6") (pin "32") (pinfunction "VDD_IO_32") (pintype "bidirectional"))
      (node (ref "U6") (pin "47") (pinfunction "VDD_IO_47") (pintype "bidirectional"))
      (node (ref "U7") (pin "8") (pinfunction "VCC_8") (pintype "bidirectional"))
      (node (ref "Y2") (pin "1") (pinfunction "EN_1") (pintype "passive"))
      (node (ref "Y2") (pin "4") (pinfunction "VDD_4") (pintype "passive"))
    )
    (net (code "3") (name "16MHZ_IN") (class "Default")
      (node (ref "C30") (pin "P$1") (pinfunction "P$1_P$1") (pintype "passive"))
      (node (ref "R16") (pin "P$1") (pinfunction "P$1_P$1") (pintype "passive"))
      (node (ref "U6") (pin "9") (pinfunction "XTAL_IN_9") (pintype "bidirectional"))
      (node (ref "Y1") (pin "1") (pinfunction "IN_1") (pintype "passive"))
    )
    (net (code "4") (name "16MHZ_OUT") (class "Default")
      (node (ref "C31") (pin "P$1") (pinfunction "P$1_P$1") (pintype "passive"))
      (node (ref "R16") (pin "P$2") (pinfunction "P$2_P$2") (pintype "passive"))
      (node (ref "U6") (pin "10") (pinfunction "XTAL_OUT_10") (pintype "bidirectional"))
      (node (ref "Y1") (pin "3") (pinfunction "OUT_3") (pintype "passive"))
    )
    (net (code "5") (name "32KHZ_CLK") (class "Default")
      (node (ref "U6") (pin "20") (pinfunction "AON_PSD_LFALTCLK_20") (pintype "bidirectional"))
      (node (ref "Y2") (pin "3") (pinfunction "OUT_3") (pintype "passive"))
    )
    (net (code "6") (name "CGND") (class "Default")
      (node (ref "J1") (pin "S1") (pinfunction "SLD_S1") (pintype "power_in"))
      (node (ref "J1") (pin "S2") (pinfunction "SLD_S2") (pintype "power_in"))
      (node (ref "J1") (pin "S3") (pinfunction "SLD_S3") (pintype "power_in"))
      (node (ref "J1") (pin "S4") (pinfunction "SLD_S4") (pintype "power_in"))
      (node (ref "J1") (pin "S5") (pinfunction "SLD_S5") (pintype "power_in"))
      (node (ref "J1") (pin "S6") (pinfunction "SLD_S6") (pintype "power_in"))
      (node (ref "MGT1") (pin "P$1") (pinfunction "P$1_P$1") (pintype "bidirectional"))
      (node (ref "R20") (pin "P$1") (pinfunction "P$1_P$1") (pintype "passive"))
    )
    (net (code "7") (name "CS0") (class "Default")
      (node (ref "J3") (pin "P$3") (pinfunction "PIN3_P$3") (pintype "bidirectional"))
      (node (ref "U6") (pin "27") (pinfunction "IO2_27") (pintype "bidirectional"))
    )
    (net (code "8") (name "DBG_RESET") (class "Default")
      (node (ref "J2") (pin "3") (pinfunction "3_3") (pintype "passive"))
      (node (ref "R8") (pin "P$2") (pinfunction "P$2_P$2") (pintype "passive"))
      (node (ref "U5") (pin "34") (pinfunction "RESET_B_34") (pintype "bidirectional"))
    )
    (net (code "9") (name "DBG_SWDCLK") (class "Default")
      (node (ref "J2") (pin "4") (pinfunction "4_4") (pintype "passive"))
      (node (ref "U5") (pin "22") (pinfunction "PTA0_22") (pintype "bidirectional"))
    )
    (net (code "10") (name "DBG_SWDIO") (class "Default")
      (node (ref "J2") (pin "2") (pinfunction "2_2") (pintype "passive"))
      (node (ref "U5") (pin "25") (pinfunction "PTA3_25") (pintype "bidirectional"))
    )
    (net (code "11") (name "DBG_SWO") (class "Default")
      (node (ref "J2") (pin "6") (pinfunction "6_6") (pintype "passive"))
      (node (ref "U5") (pin "24") (pinfunction "PTA2_24") (pintype "bidirectional"))
    )
    (net (code "12") (name "GND") (class "Default")
      (node (ref "C1") (pin "P$2") (pinfunction "P$2_P$2") (pintype "passive"))
      (node (ref "C10") (pin "P$2") (pinfunction "P$2_P$2") (pintype "passive"))
      (node (ref "C11") (pin "P$2") (pinfunction "P$2_P$2") (pintype "passive"))
      (node (ref "C12") (pin "P$2") (pinfunction "P$2_P$2") (pintype "passive"))
      (node (ref "C15") (pin "P$2") (pinfunction "P$2_P$2") (pintype "passive"))
      (node (ref "C16") (pin "P$2") (pinfunction "P$2_P$2") (pintype "passive"))
      (node (ref "C17") (pin "P$2") (pinfunction "P$2_P$2") (pintype "passive"))
      (node (ref "C18") (pin "P$2") (pinfunction "P$2_P$2") (pintype "passive"))
      (node (ref "C19") (pin "P$2") (pinfunction "P$2_P$2") (pintype "passive"))
      (node (ref "C2") (pin "P$2") (pinfunction "P$2_P$2") (pintype "passive"))
      (node (ref "C20") (pin "P$2") (pinfunction "P$2_P$2") (pintype "passive"))
      (node (ref "C21") (pin "P$2") (pinfunction "P$2_P$2") (pintype "passive"))
      (node (ref "C22") (pin "P$2") (pinfunction "P$2_P$2") (pintype "passive"))
      (node (ref "C23") (pin "P$2") (pinfunction "P$2_P$2") (pintype "passive"))
      (node (ref "C24") (pin "P$2") (pinfunction "P$2_P$2") (pintype "passive"))
      (node (ref "C25") (pin "P$2") (pinfunction "P$2_P$2") (pintype "passive"))
      (node (ref "C26") (pin "P$2") (pinfunction "P$2_P$2") (pintype "passive"))
      (node (ref "C27") (pin "P$2") (pinfunction "P$2_P$2") (pintype "passive"))
      (node (ref "C28") (pin "P$2") (pinfunction "P$2_P$2") (pintype "passive"))
      (node (ref "C29") (pin "P$2") (pinfunction "P$2_P$2") (pintype "passive"))
      (node (ref "C3") (pin "P$2") (pinfunction "P$2_P$2") (pintype "passive"))
      (node (ref "C30") (pin "P$2") (pinfunction "P$2_P$2") (pintype "passive"))
      (node (ref "C31") (pin "P$2") (pinfunction "P$2_P$2") (pintype "passive"))
      (node (ref "C32") (pin "P$2") (pinfunction "P$2_P$2") (pintype "passive"))
      (node (ref "C4") (pin "P$2") (pinfunction "P$2_P$2") (pintype "passive"))
      (node (ref "C5") (pin "P$2") (pinfunction "P$2_P$2") (pintype "passive"))
      (node (ref "C6") (pin "P$2") (pinfunction "P$2_P$2") (pintype "passive"))
      (node (ref "C7") (pin "P$2") (pinfunction "P$2_P$2") (pintype "passive"))
      (node (ref "C8") (pin "P$2") (pinfunction "P$2_P$2") (pintype "passive"))
      (node (ref "C9") (pin "P$2") (pinfunction "P$2_P$2") (pintype "passive"))
      (node (ref "D4") (pin "1") (pinfunction "A_1") (pintype "passive"))
      (node (ref "D5") (pin "1") (pinfunction "A_1") (pintype "passive"))
      (node (ref "J1") (pin "5") (pinfunction "GND_5") (pintype "power_in"))
      (node (ref "J2") (pin "5") (pinfunction "5_5") (pintype "passive"))
      (node (ref "J3") (pin "P$8") (pinfunction "PIN8_P$8") (pintype "bidirectional"))
      (node (ref "J4") (pin "P$8") (pinfunction "PIN8_P$8") (pintype "bidirectional"))
      (node (ref "MGT2") (pin "P$1") (pinfunction "P$1_P$1") (pintype "bidirectional"))
      (node (ref "R15") (pin "P$2") (pinfunction "P$2_P$2") (pintype "passive"))
      (node (ref "R2") (pin "P$1") (pinfunction "P$1_P$1") (pintype "passive"))
      (node (ref "R20") (pin "P$2") (pinfunction "P$2_P$2") (pintype "passive"))
      (node (ref "R4") (pin "P$2") (pinfunction "P$2_P$2") (pintype "passive"))
      (node (ref "R7") (pin "P$1") (pinfunction "P$1_P$1") (pintype "passive"))
      (node (ref "SW1") (pin "P$1") (pinfunction "P$1_P$1") (pintype "bidirectional"))
      (node (ref "SW1") (pin "P$2") (pinfunction "P$2_P$2") (pintype "bidirectional"))
      (node (ref "SW2") (pin "P$1") (pinfunction "P$1_P$1") (pintype "bidirectional"))
      (node (ref "SW2") (pin "P$2") (pinfunction "P$2_P$2") (pintype "bidirectional"))
      (node (ref "U1") (pin "1") (pinfunction "GND/1_1") (pintype "passive"))
      (node (ref "U2") (pin "2") (pinfunction "VSS_2") (pintype "power_in"))
      (node (ref "U3") (pin "2") (pinfunction "GND_2") (pintype "power_in"))
      (node (ref "U4") (pin "2") (pinfunction "GND_2") (pintype "passive"))
      (node (ref "U5") (pin "15") (pinfunction "VREFL_15") (pintype "bidirectional"))
      (node (ref "U5") (pin "16") (pinfunction "VSSA_16") (pintype "bidirectional"))
      (node (ref "U5") (pin "31") (pinfunction "GND_31") (pintype "bidirectional"))
      (node (ref "U5") (pin "4") (pinfunction "GND_4") (pintype "bidirectional"))
      (node (ref "U5") (pin "47") (pinfunction "GND_47") (pintype "bidirectional"))
      (node (ref "U6") (pin "49") (pinfunction "GND_49") (pintype "bidirectional"))
      (node (ref "U7") (pin "4") (pinfunction "GND_4") (pintype "bidirectional"))
      (node (ref "X1") (pin "2") (pinfunction "2_2") (pintype "passive"))
      (node (ref "Y1") (pin "2") (pinfunction "2_2") (pintype "passive"))
      (node (ref "Y1") (pin "4") (pinfunction "4_4") (pintype "passive"))
      (node (ref "Y2") (pin "2") (pinfunction "GND_2") (pintype "passive"))
    )
    (net (code "13") (name "IO1") (class "Default")
      (node (ref "J4") (pin "P$2") (pinfunction "PIN2_P$2") (pintype "bidirectional"))
      (node (ref "U6") (pin "26") (pinfunction "IO1_26") (pintype "bidirectional"))
    )
    (net (code "14") (name "IO9") (class "Default")
      (node (ref "J5") (pin "P$1") (pinfunction "PIN1_P$1") (pintype "bidirectional"))
      (node (ref "U6") (pin "33") (pinfunction "IO9_33") (pintype "bidirectional"))
    )
    (net (code "15") (name "IO10") (class "Default")
      (node (ref "J5") (pin "P$2") (pinfunction "PIN2_P$2") (pintype "bidirectional"))
      (node (ref "U6") (pin "34") (pinfunction "IO10_34") (pintype "bidirectional"))
    )
    (net (code "16") (name "IO11") (class "Default")
      (node (ref "J5") (pin "P$3") (pinfunction "PIN3_P$3") (pintype "bidirectional"))
      (node (ref "U6") (pin "35") (pinfunction "IO11_35") (pintype "bidirectional"))
    )
    (net (code "17") (name "IO19") (class "Default")
      (node (ref "J5") (pin "P$4") (pinfunction "PIN4_P$4") (pintype "bidirectional"))
      (node (ref "U6") (pin "41") (pinfunction "IO19_41") (pintype "bidirectional"))
    )
    (net (code "18") (name "IO20") (class "Default")
      (node (ref "J5") (pin "P$5") (pinfunction "PIN5_P$5") (pintype "bidirectional"))
      (node (ref "U6") (pin "42") (pinfunction "IO20_42") (pintype "bidirectional"))
    )
    (net (code "19") (name "IO21") (class "Default")
      (node (ref "J5") (pin "P$6") (pinfunction "PIN6_P$6") (pintype "bidirectional"))
      (node (ref "U6") (pin "43") (pinfunction "IO21_43") (pintype "bidirectional"))
    )
    (net (code "20") (name "IO22") (class "Default")
      (node (ref "J5") (pin "P$7") (pinfunction "PIN7_P$7") (pintype "bidirectional"))
      (node (ref "U6") (pin "44") (pinfunction "IO22_44") (pintype "bidirectional"))
    )
    (net (code "21") (name "JTAG_TCK") (class "Default")
      (node (ref "R10") (pin "P$2") (pinfunction "P$2_P$2") (pintype "passive"))
      (node (ref "U6") (pin "13") (pinfunction "JTAG_TCK_13") (pintype "bidirectional"))
    )
    (net (code "22") (name "JTAG_TDI") (class "Default")
      (node (ref "R9") (pin "P$2") (pinfunction "P$2_P$2") (pintype "passive"))
      (node (ref "U6") (pin "16") (pinfunction "JTAG_TDI_16") (pintype "bidirectional"))
    )
    (net (code "23") (name "JTAG_TDO") (class "Default")
      (node (ref "U5") (pin "2") (pinfunction "PTE1/LLWU_P0_2") (pintype "bidirectional"))
      (node (ref "U6") (pin "14") (pinfunction "JTAG_TDO_14") (pintype "bidirectional"))
    )
    (net (code "24") (name "JTAG_TMS") (class "Default")
      (node (ref "R11") (pin "P$1") (pinfunction "P$1_P$1") (pintype "passive"))
      (node (ref "U6") (pin "15") (pinfunction "JTAG_TMS_15") (pintype "bidirectional"))
    )
    (net (code "25") (name "MISO") (class "Default")
      (node (ref "J3") (pin "P$5") (pinfunction "PIN5_P$5") (pintype "bidirectional"))
      (node (ref "U6") (pin "29") (pinfunction "IO4_29") (pintype "bidirectional"))
    )
    (net (code "26") (name "MOSI") (class "Default")
      (node (ref "J3") (pin "P$6") (pinfunction "PIN6_P$6") (pintype "bidirectional"))
      (node (ref "U6") (pin "28") (pinfunction "IO3_28") (pintype "bidirectional"))
    )
    (net (code "27") (name "Net-(D1-PadCATHODE)") (class "Default")
      (node (ref "D1") (pin "CATHODE") (pinfunction "CATHODE_CATHODE") (pintype "power_in"))
      (node (ref "R1") (pin "P$1") (pinfunction "P$1_P$1") (pintype "passive"))
    )
    (net (code "28") (name "Net-(D2-PadCATHODE)") (class "Default")
      (node (ref "D2") (pin "CATHODE") (pinfunction "CATHODE_CATHODE") (pintype "power_in"))
      (node (ref "R4") (pin "P$1") (pinfunction "P$1_P$1") (pintype "passive"))
    )
    (net (code "29") (name "Net-(U2-PROG)") (class "Default")
      (node (ref "R2") (pin "P$2") (pinfunction "P$2_P$2") (pintype "passive"))
      (node (ref "U2") (pin "5") (pinfunction "PROG_5") (pintype "input"))
    )
    (net (code "30") (name "Net-(U2-STAT)") (class "Default")
      (node (ref "R1") (pin "P$2") (pinfunction "P$2_P$2") (pintype "passive"))
      (node (ref "U2") (pin "1") (pinfunction "STAT_1") (pintype "output"))
    )
    (net (code "31") (name "Net-(U3-EN)") (class "Default")
      (node (ref "R3") (pin "P$1") (pinfunction "P$1_P$1") (pintype "passive"))
      (node (ref "U3") (pin "3") (pinfunction "EN_3") (pintype "input"))
    )
    (net (code "32") (name "Net-(U4-EN)") (class "Default")
      (node (ref "C7") (pin "P$1") (pinfunction "P$1_P$1") (pintype "passive"))
      (node (ref "R5") (pin "P$2") (pinfunction "P$2_P$2") (pintype "passive"))
      (node (ref "R6") (pin "P$1") (pinfunction "P$1_P$1") (pintype "passive"))
      (node (ref "R7") (pin "P$2") (pinfunction "P$2_P$2") (pintype "passive"))
      (node (ref "U4") (pin "3") (pinfunction "EN_3") (pintype "passive"))
    )
    (net (code "33") (name "Net-(U5-PTB0{slash}LLWU_P5)") (class "Default")
      (node (ref "B0") (pin "TP") (pinfunction "TP_TP") (pintype "input"))
      (node (ref "U5") (pin "35") (pinfunction "PTB0/LLWU_P5_35") (pintype "bidirectional"))
    )
    (net (code "34") (name "Net-(U5-PTB1)") (class "Default")
      (node (ref "B1") (pin "TP") (pinfunction "TP_TP") (pintype "input"))
      (node (ref "U5") (pin "36") (pinfunction "PTB1_36") (pintype "bidirectional"))
    )
    (net (code "35") (name "Net-(U5-PTB2)") (class "Default")
      (node (ref "B2") (pin "TP") (pinfunction "TP_TP") (pintype "input"))
      (node (ref "U5") (pin "37") (pinfunction "PTB2_37") (pintype "bidirectional"))
    )
    (net (code "36") (name "Net-(U5-PTB3)") (class "Default")
      (node (ref "B3") (pin "TP") (pinfunction "TP_TP") (pintype "input"))
      (node (ref "U5") (pin "38") (pinfunction "PTB3_38") (pintype "bidirectional"))
    )
    (net (code "37") (name "Net-(U5-PTD2{slash}LLWU_P13)") (class "Default")
      (node (ref "R9") (pin "P$1") (pinfunction "P$1_P$1") (pintype "passive"))
      (node (ref "U5") (pin "59") (pinfunction "PTD2/LLWU_P13_59") (pintype "bidirectional"))
    )
    (net (code "38") (name "Net-(U5-PTD5)") (class "Default")
      (node (ref "R10") (pin "P$1") (pinfunction "P$1_P$1") (pintype "passive"))
      (node (ref "U5") (pin "62") (pinfunction "PTD5_62") (pintype "bidirectional"))
    )
    (net (code "39") (name "Net-(U5-PTD6{slash}LLWU_P15)") (class "Default")
      (node (ref "R11") (pin "P$2") (pinfunction "P$2_P$2") (pintype "passive"))
      (node (ref "U5") (pin "63") (pinfunction "PTD6/LLWU_P15_63") (pintype "bidirectional"))
    )
    (net (code "40") (name "Net-(U6-AON_PSD_LFCLKSEL)") (class "Default")
      (node (ref "R15") (pin "P$1") (pinfunction "P$1_P$1") (pintype "passive"))
      (node (ref "U6") (pin "21") (pinfunction "AON_PSD_LFCLKSEL_21") (pintype "bidirectional"))
    )
    (net (code "41") (name "Net-(U6-PLL_AVSS)") (class "Default")
      (node (ref "C13") (pin "P$2") (pinfunction "P$2_P$2") (pintype "passive"))
      (node (ref "C14") (pin "P$2") (pinfunction "P$2_P$2") (pintype "passive"))
      (node (ref "U6") (pin "8") (pinfunction "PLL_AVSS_8") (pintype "bidirectional"))
    )
    (net (code "42") (name "PLL_AVDD") (class "Default")
      (node (ref "C13") (pin "P$1") (pinfunction "P$1_P$1") (pintype "passive"))
      (node (ref "C14") (pin "P$1") (pinfunction "P$1_P$1") (pintype "passive"))
      (node (ref "R12") (pin "P$2") (pinfunction "P$2_P$2") (pintype "passive"))
      (node (ref "U6") (pin "7") (pinfunction "PLL_AVDD_7") (pintype "bidirectional"))
    )
    (net (code "43") (name "PWM") (class "Default")
      (node (ref "J4") (pin "P$1") (pinfunction "PIN1_P$1") (pintype "bidirectional"))
      (node (ref "U6") (pin "25") (pinfunction "IO0_25") (pintype "bidirectional"))
    )
    (net (code "44") (name "QSPI_CS") (class "Default")
      (node (ref "R19") (pin "P$2") (pinfunction "P$2_P$2") (pintype "passive"))
      (node (ref "U6") (pin "5") (pinfunction "QSPI_CS_5") (pintype "bidirectional"))
      (node (ref "U7") (pin "1") (pinfunction "CE#_1") (pintype "bidirectional"))
    )
    (net (code "45") (name "QSPI_DQ0") (class "Default")
      (node (ref "U6") (pin "4") (pinfunction "QSPI_DQ_0_4") (pintype "bidirectional"))
      (node (ref "U7") (pin "5") (pinfunction "MOSI/IO0_5") (pintype "bidirectional"))
    )
    (net (code "46") (name "QSPI_DQ1") (class "Default")
      (node (ref "U6") (pin "3") (pinfunction "QSPI_DQ_1_3") (pintype "bidirectional"))
      (node (ref "U7") (pin "2") (pinfunction "MISO/IO1_2") (pintype "bidirectional"))
    )
    (net (code "47") (name "QSPI_DQ2") (class "Default")
      (node (ref "R17") (pin "P$2") (pinfunction "P$2_P$2") (pintype "passive"))
      (node (ref "U6") (pin "2") (pinfunction "QSPI_DQ_2_2") (pintype "bidirectional"))
      (node (ref "U7") (pin "3") (pinfunction "WP#/IO2_3") (pintype "bidirectional"))
    )
    (net (code "48") (name "QSPI_DQ3") (class "Default")
      (node (ref "R18") (pin "P$2") (pinfunction "P$2_P$2") (pintype "passive"))
      (node (ref "U6") (pin "1") (pinfunction "QSPI_DQ_3_1") (pintype "bidirectional"))
      (node (ref "U7") (pin "7") (pinfunction "HOLD#/IO3_7") (pintype "bidirectional"))
    )
    (net (code "49") (name "QSPI_SCK") (class "Default")
      (node (ref "U6") (pin "48") (pinfunction "QSPI_SCK_48") (pintype "bidirectional"))
      (node (ref "U7") (pin "6") (pinfunction "SCK_6") (pintype "bidirectional"))
    )
    (net (code "50") (name "RESET") (class "Default")
      (node (ref "C28") (pin "P$1") (pinfunction "P$1_P$1") (pintype "passive"))
      (node (ref "D5") (pin "2") (pinfunction "C_2") (pintype "passive"))
      (node (ref "J3") (pin "P$2") (pinfunction "PIN2_P$2") (pintype "bidirectional"))
      (node (ref "R14") (pin "P$2") (pinfunction "P$2_P$2") (pintype "passive"))
      (node (ref "SW2") (pin "P$3") (pinfunction "P$3_P$3") (pintype "bidirectional"))
      (node (ref "SW2") (pin "P$4") (pinfunction "P$4_P$4") (pintype "bidirectional"))
      (node (ref "U5") (pin "64") (pinfunction "PTD7_64") (pintype "bidirectional"))
      (node (ref "U6") (pin "24") (pinfunction "AON_ERST_N_24") (pintype "bidirectional"))
    )
    (net (code "51") (name "RXI") (class "Default")
      (node (ref "J4") (pin "P$3") (pinfunction "PIN3_P$3") (pintype "bidirectional"))
      (node (ref "U6") (pin "45") (pinfunction "IO23_45") (pintype "bidirectional"))
    )
    (net (code "52") (name "SCK") (class "Default")
      (node (ref "J3") (pin "P$4") (pinfunction "PIN4_P$4") (pintype "bidirectional"))
      (node (ref "U6") (pin "31") (pinfunction "IO5_31") (pintype "bidirectional"))
    )
    (net (code "53") (name "SCL") (class "Default")
      (node (ref "J4") (pin "P$5") (pinfunction "PIN5_P$5") (pintype "bidirectional"))
      (node (ref "U6") (pin "37") (pinfunction "IO13_37") (pintype "bidirectional"))
    )
    (net (code "54") (name "SDA") (class "Default")
      (node (ref "J4") (pin "P$6") (pinfunction "PIN6_P$6") (pintype "bidirectional"))
      (node (ref "U6") (pin "36") (pinfunction "IO12_36") (pintype "bidirectional"))
    )
    (net (code "55") (name "TXO") (class "Default")
      (node (ref "J4") (pin "P$4") (pinfunction "PIN4_P$4") (pintype "bidirectional"))
      (node (ref "U6") (pin "40") (pinfunction "IO18_40") (pintype "bidirectional"))
    )
    (net (code "56") (name "UART_RX_MK22") (class "Default")
      (node (ref "U5") (pin "39") (pinfunction "PTB16_39") (pintype "bidirectional"))
      (node (ref "U6") (pin "39") (pinfunction "IO17_39") (pintype "bidirectional"))
    )
    (net (code "57") (name "UART_TX_MK22") (class "Default")
      (node (ref "U5") (pin "40") (pinfunction "PTB17_40") (pintype "bidirectional"))
      (node (ref "U6") (pin "38") (pinfunction "IO16_38") (pintype "bidirectional"))
    )
    (net (code "58") (name "USB_N") (class "Default")
      (node (ref "J1") (pin "2") (pinfunction "D-_2") (pintype "bidirectional"))
      (node (ref "U1") (pin "2") (pinfunction "2_2") (pintype "passive"))
      (node (ref "U5") (pin "6") (pinfunction "D-_6") (pintype "bidirectional"))
    )
    (net (code "59") (name "USB_P") (class "Default")
      (node (ref "J1") (pin "3") (pinfunction "D+_3") (pintype "bidirectional"))
      (node (ref "U1") (pin "3") (pinfunction "3_3") (pintype "passive"))
      (node (ref "U5") (pin "5") (pinfunction "D+_5") (pintype "bidirectional"))
    )
    (net (code "60") (name "VDD_CORE_EN") (class "Default")
      (node (ref "R5") (pin "P$1") (pinfunction "P$1_P$1") (pintype "passive"))
      (node (ref "U6") (pin "22") (pinfunction "AON_PMU_OUT_0_22") (pintype "bidirectional"))
    )
    (net (code "61") (name "V_BATT") (class "Default")
      (node (ref "C1") (pin "P$1") (pinfunction "P$1_P$1") (pintype "passive"))
      (node (ref "D3") (pin "A") (pinfunction "A_A") (pintype "passive"))
      (node (ref "U2") (pin "3") (pinfunction "VBAT_3") (pintype "power_in"))
      (node (ref "X1") (pin "1") (pinfunction "1_1") (pintype "passive"))
    )
    (net (code "62") (name "V_USB") (class "Default")
      (node (ref "C2") (pin "P$1") (pinfunction "P$1_P$1") (pintype "passive"))
      (node (ref "C3") (pin "P$1") (pinfunction "P$1_P$1") (pintype "passive"))
      (node (ref "D1") (pin "ANODE") (pinfunction "ANODE_ANODE") (pintype "power_in"))
      (node (ref "D3") (pin "C") (pinfunction "C_C") (pintype "passive"))
      (node (ref "J1") (pin "1") (pinfunction "5V_1") (pintype "power_in"))
      (node (ref "J4") (pin "P$7") (pinfunction "PIN7_P$7") (pintype "bidirectional"))
      (node (ref "R3") (pin "P$2") (pinfunction "P$2_P$2") (pintype "passive"))
      (node (ref "U1") (pin "4") (pinfunction "VDD/4_4") (pintype "passive"))
      (node (ref "U2") (pin "4") (pinfunction "VDD_4") (pintype "power_in"))
      (node (ref "U3") (pin "1") (pinfunction "IN_1") (pintype "power_in"))
    )
    (net (code "63") (name "WAKE") (class "Default")
      (node (ref "D4") (pin "2") (pinfunction "C_2") (pintype "passive"))
      (node (ref "J3") (pin "P$1") (pinfunction "PIN1_P$1") (pintype "bidirectional"))
      (node (ref "R13") (pin "P$2") (pinfunction "P$2_P$2") (pintype "passive"))
      (node (ref "SW1") (pin "P$3") (pinfunction "P$3_P$3") (pintype "bidirectional"))
      (node (ref "SW1") (pin "P$4") (pinfunction "P$4_P$4") (pintype "bidirectional"))
      (node (ref "U6") (pin "18") (pinfunction "AON_DWAKEUP_N_18") (pintype "bidirectional"))
    )
    (net (code "64") (name "unconnected-(J1-ID-Pad4)") (class "Default")
      (node (ref "J1") (pin "4") (pinfunction "ID_4") (pintype "bidirectional"))
    )
    (net (code "65") (name "unconnected-(U3-P4-Pad4)") (class "Default")
      (node (ref "U3") (pin "4") (pinfunction "P4_4") (pintype "bidirectional"))
    )
    (net (code "66") (name "unconnected-(U4-NC-Pad4)") (class "Default")
      (node (ref "U4") (pin "4") (pinfunction "NC_4") (pintype "passive"))
    )
    (net (code "67") (name "unconnected-(U5-ADC0_DM0{slash}ADC1_DM3-Pad10)") (class "Default")
      (node (ref "U5") (pin "10") (pinfunction "ADC0_DM0/ADC1_DM3_10") (pintype "bidirectional"))
    )
    (net (code "68") (name "unconnected-(U5-ADC0_DP0{slash}ADC1_DP3-Pad9)") (class "Default")
      (node (ref "U5") (pin "9") (pinfunction "ADC0_DP0/ADC1_DP3_9") (pintype "bidirectional"))
    )
    (net (code "69") (name "unconnected-(U5-ADC1_DM0{slash}ADC0_DM3-Pad12)") (class "Default")
      (node (ref "U5") (pin "12") (pinfunction "ADC1_DM0/ADC0_DM3_12") (pintype "bidirectional"))
    )
    (net (code "70") (name "unconnected-(U5-ADC1_DP0{slash}ADC0_DP3-Pad11)") (class "Default")
      (node (ref "U5") (pin "11") (pinfunction "ADC1_DP0/ADC0_DP3_11") (pintype "bidirectional"))
    )
    (net (code "71") (name "unconnected-(U5-DAC0_OUT-Pad18)") (class "Default")
      (node (ref "U5") (pin "18") (pinfunction "DAC0_OUT_18") (pintype "bidirectional"))
    )
    (net (code "72") (name "unconnected-(U5-EXTAL32-Pad20)") (class "Default")
      (node (ref "U5") (pin "20") (pinfunction "EXTAL32_20") (pintype "bidirectional"))
    )
    (net (code "73") (name "unconnected-(U5-NC8-Pad8)") (class "Default")
      (node (ref "U5") (pin "8") (pinfunction "NC8_8") (pintype "bidirectional"))
    )
    (net (code "74") (name "unconnected-(U5-PTA1-Pad23)") (class "Default")
      (node (ref "U5") (pin "23") (pinfunction "PTA1_23") (pintype "bidirectional"))
    )
    (net (code "75") (name "unconnected-(U5-PTA5-Pad27)") (class "Default")
      (node (ref "U5") (pin "27") (pinfunction "PTA5_27") (pintype "bidirectional"))
    )
    (net (code "76") (name "unconnected-(U5-PTA12-Pad28)") (class "Default")
      (node (ref "U5") (pin "28") (pinfunction "PTA12_28") (pintype "bidirectional"))
    )
    (net (code "77") (name "unconnected-(U5-PTA13{slash}LLWU_P4-Pad29)") (class "Default")
      (node (ref "U5") (pin "29") (pinfunction "PTA13/LLWU_P4_29") (pintype "bidirectional"))
    )
    (net (code "78") (name "unconnected-(U5-PTA18-Pad32)") (class "Default")
      (node (ref "U5") (pin "32") (pinfunction "PTA18_32") (pintype "bidirectional"))
    )
    (net (code "79") (name "unconnected-(U5-PTA19-Pad33)") (class "Default")
      (node (ref "U5") (pin "33") (pinfunction "PTA19_33") (pintype "bidirectional"))
    )
    (net (code "80") (name "unconnected-(U5-PTB18-Pad41)") (class "Default")
      (node (ref "U5") (pin "41") (pinfunction "PTB18_41") (pintype "bidirectional"))
    )
    (net (code "81") (name "unconnected-(U5-PTB19-Pad42)") (class "Default")
      (node (ref "U5") (pin "42") (pinfunction "PTB19_42") (pintype "bidirectional"))
    )
    (net (code "82") (name "unconnected-(U5-PTC0-Pad43)") (class "Default")
      (node (ref "U5") (pin "43") (pinfunction "PTC0_43") (pintype "bidirectional"))
    )
    (net (code "83") (name "unconnected-(U5-PTC1{slash}LLWU_P6-Pad44)") (class "Default")
      (node (ref "U5") (pin "44") (pinfunction "PTC1/LLWU_P6_44") (pintype "bidirectional"))
    )
    (net (code "84") (name "unconnected-(U5-PTC2-Pad45)") (class "Default")
      (node (ref "U5") (pin "45") (pinfunction "PTC2_45") (pintype "bidirectional"))
    )
    (net (code "85") (name "unconnected-(U5-PTC3{slash}LLWU_P7-Pad46)") (class "Default")
      (node (ref "U5") (pin "46") (pinfunction "PTC3/LLWU_P7_46") (pintype "bidirectional"))
    )
    (net (code "86") (name "unconnected-(U5-PTC4{slash}LLWU_P8-Pad49)") (class "Default")
      (node (ref "U5") (pin "49") (pinfunction "PTC4/LLWU_P8_49") (pintype "bidirectional"))
    )
    (net (code "87") (name "unconnected-(U5-PTC5{slash}LLWU_P9-Pad50)") (class "Default")
      (node (ref "U5") (pin "50") (pinfunction "PTC5/LLWU_P9_50") (pintype "bidirectional"))
    )
    (net (code "88") (name "unconnected-(U5-PTC6{slash}LLWU_P10-Pad51)") (class "Default")
      (node (ref "U5") (pin "51") (pinfunction "PTC6/LLWU_P10_51") (pintype "bidirectional"))
    )
    (net (code "89") (name "unconnected-(U5-PTC7-Pad52)") (class "Default")
      (node (ref "U5") (pin "52") (pinfunction "PTC7_52") (pintype "bidirectional"))
    )
    (net (code "90") (name "unconnected-(U5-PTC8-Pad53)") (class "Default")
      (node (ref "U5") (pin "53") (pinfunction "PTC8_53") (pintype "bidirectional"))
    )
    (net (code "91") (name "unconnected-(U5-PTC9-Pad54)") (class "Default")
      (node (ref "U5") (pin "54") (pinfunction "PTC9_54") (pintype "bidirectional"))
    )
    (net (code "92") (name "unconnected-(U5-PTC10-Pad55)") (class "Default")
      (node (ref "U5") (pin "55") (pinfunction "PTC10_55") (pintype "bidirectional"))
    )
    (net (code "93") (name "unconnected-(U5-PTC11{slash}LLWU_P11-Pad56)") (class "Default")
      (node (ref "U5") (pin "56") (pinfunction "PTC11/LLWU_P11_56") (pintype "bidirectional"))
    )
    (net (code "94") (name "unconnected-(U5-PTD0{slash}LLWU_P12-Pad57)") (class "Default")
      (node (ref "U5") (pin "57") (pinfunction "PTD0/LLWU_P12_57") (pintype "bidirectional"))
    )
    (net (code "95") (name "unconnected-(U5-PTD1-Pad58)") (class "Default")
      (node (ref "U5") (pin "58") (pinfunction "PTD1_58") (pintype "bidirectional"))
    )
    (net (code "96") (name "unconnected-(U5-PTD3-Pad60)") (class "Default")
      (node (ref "U5") (pin "60") (pinfunction "PTD3_60") (pintype "bidirectional"))
    )
    (net (code "97") (name "unconnected-(U5-PTD4{slash}LLWU_P14-Pad61)") (class "Default")
      (node (ref "U5") (pin "61") (pinfunction "PTD4/LLWU_P14_61") (pintype "bidirectional"))
    )
    (net (code "98") (name "unconnected-(U5-PTE0{slash}VLKOUT32K-Pad1)") (class "Default")
      (node (ref "U5") (pin "1") (pinfunction "PTE0/VLKOUT32K_1") (pintype "bidirectional"))
    )
    (net (code "99") (name "unconnected-(U5-VREF_OUT-Pad17)") (class "Default")
      (node (ref "U5") (pin "17") (pinfunction "VREF_OUT_17") (pintype "bidirectional"))
    )
    (net (code "100") (name "unconnected-(U5-XTAL32-Pad19)") (class "Default")
      (node (ref "U5") (pin "19") (pinfunction "XTAL32_19") (pintype "bidirectional"))
    )
    (net (code "101") (name "unconnected-(U6-AON_PMU_OUT_1-Pad17)") (class "Default")
      (node (ref "U6") (pin "17") (pinfunction "AON_PMU_OUT_1_17") (pintype "bidirectional"))
    )
  )
)
